# amp-LNA-L-band-TQP3M9037.net
KiCad netlist of a schematic drawn in EAGLE
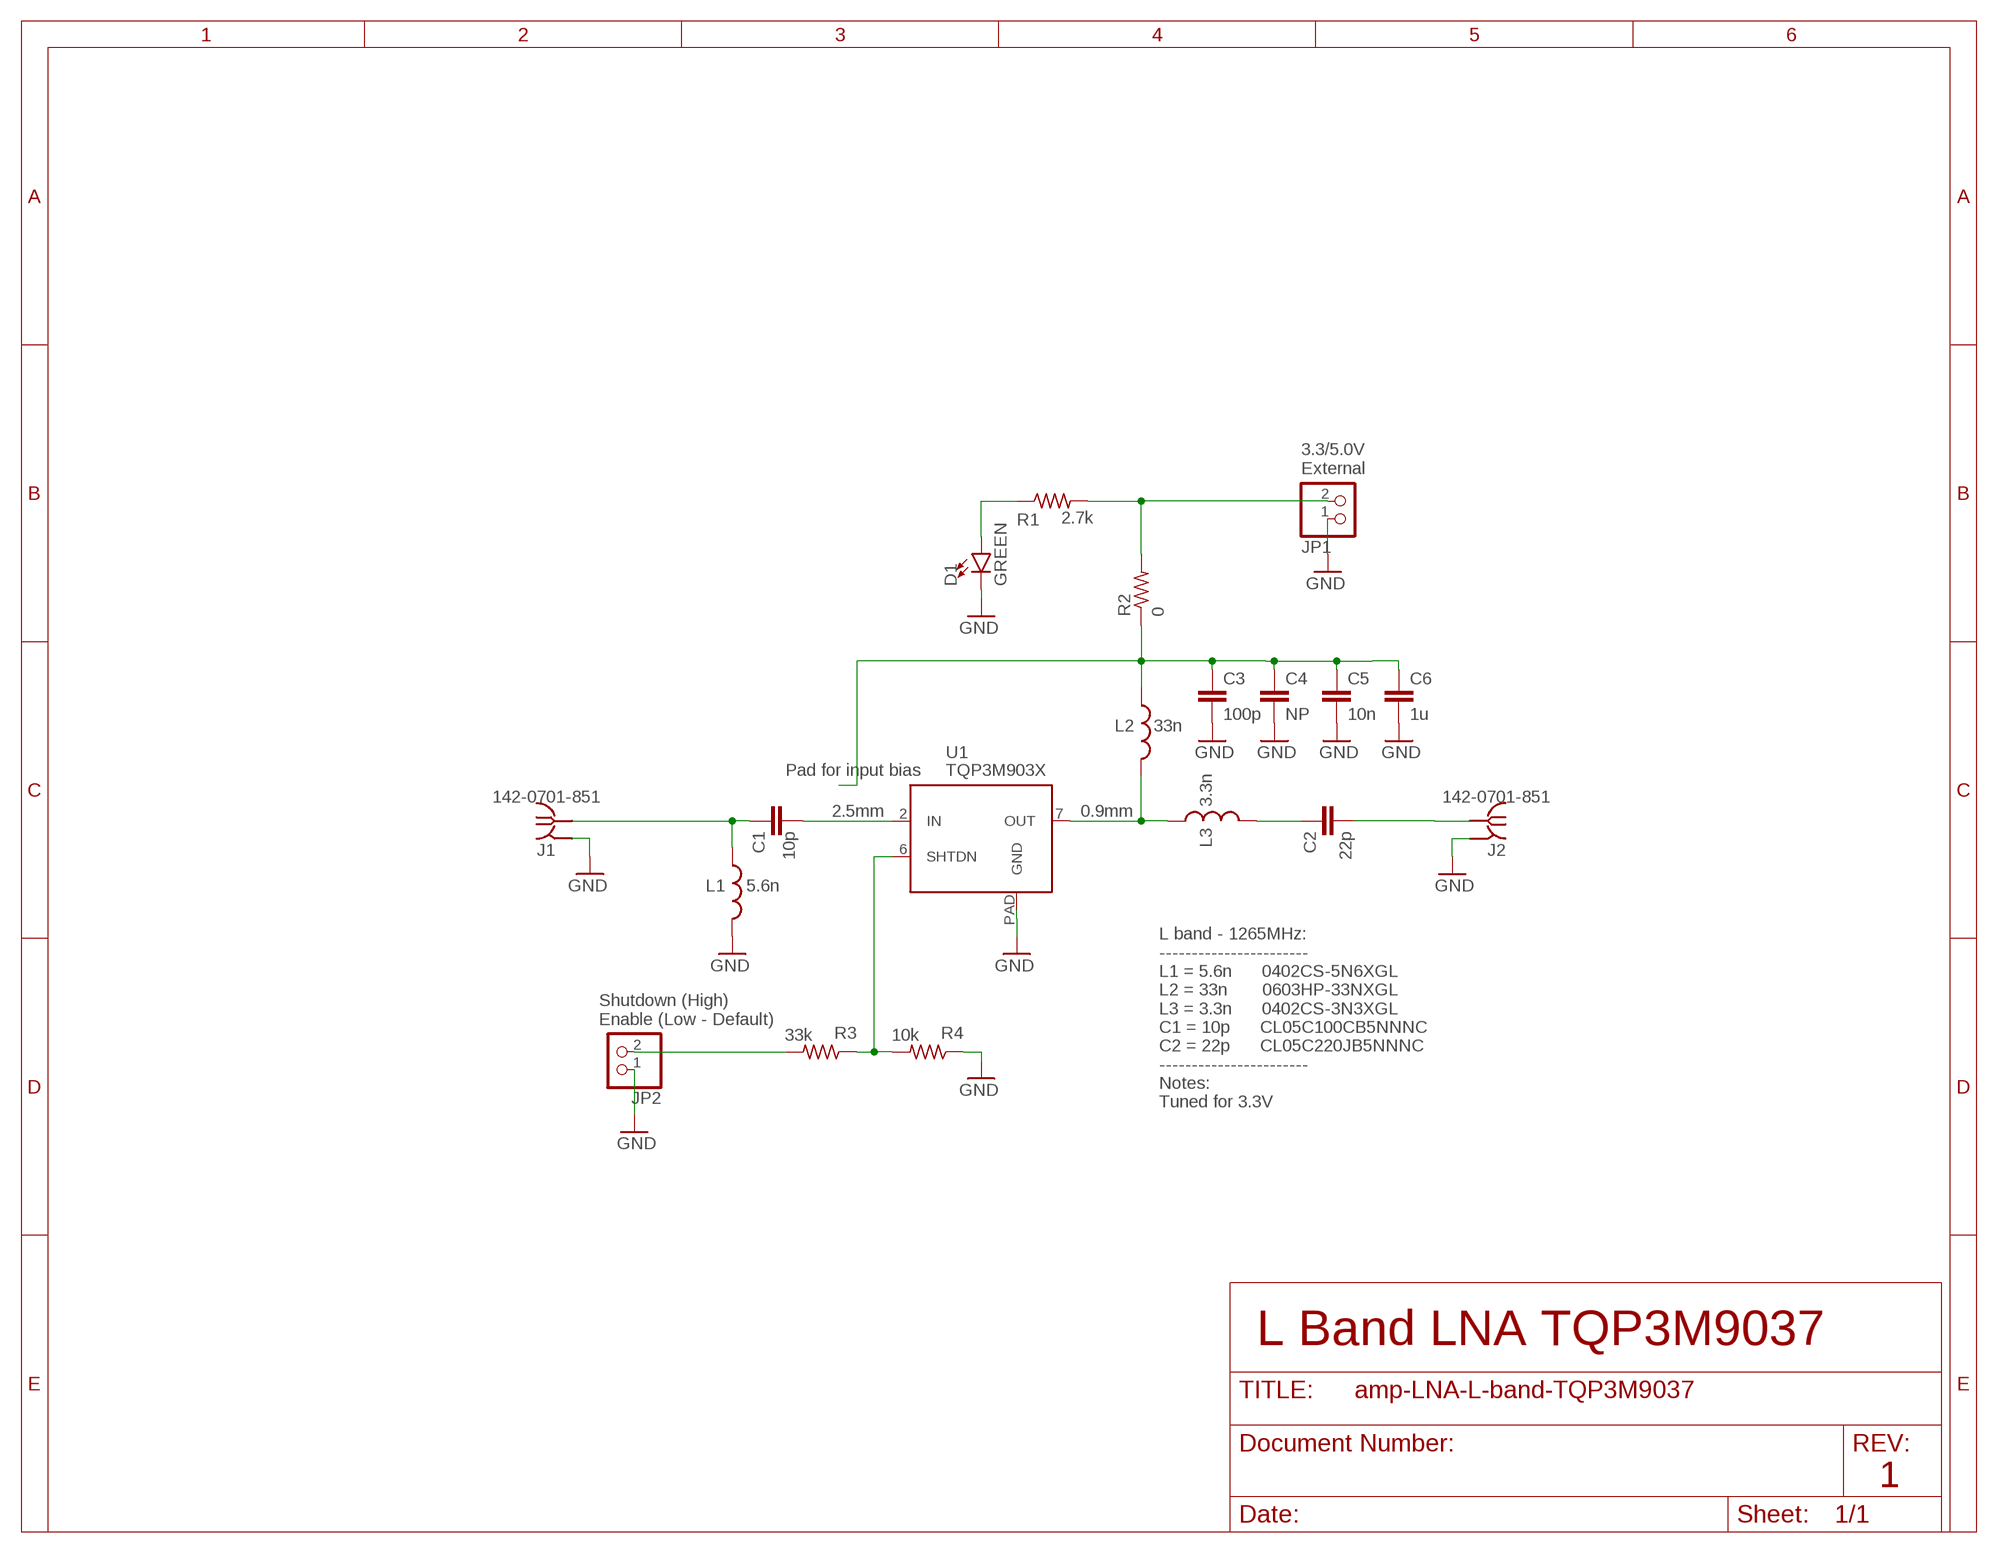
[diagram p0: schematic, sheet 1]

(export (version "E")
  (design (tool "Eeschema 10.0.6"))
  (components
    (comp (ref "C1")
      (value "10p")
      (footprint "eagle-import:.0402-C-NOSILK")
      (libsource (lib "eagle-import") (part "C-EU0402-C-NOSILK"))
    )
    (comp (ref "C2")
      (value "22p")
      (footprint "eagle-import:.0402-C-NOSILK")
      (libsource (lib "eagle-import") (part "C-EU0402-C-NOSILK"))
    )
    (comp (ref "C3")
      (value "100p")
      (footprint "eagle-import:.0603-B-NOSILK")
      (libsource (lib "eagle-import") (part "C-EU0603-B-NOSILK"))
    )
    (comp (ref "C4")
      (value "NP")
      (footprint "eagle-import:.0603-B-NOSILK")
      (libsource (lib "eagle-import") (part "C-EU0603-B-NOSILK"))
    )
    (comp (ref "C5")
      (value "10n")
      (footprint "eagle-import:.0603-B-NOSILK")
      (libsource (lib "eagle-import") (part "C-EU0603-B-NOSILK"))
    )
    (comp (ref "C6")
      (value "1u")
      (footprint "eagle-import:.0603-B-NOSILK")
      (libsource (lib "eagle-import") (part "C-EU0603-B-NOSILK"))
    )
    (comp (ref "D1")
      (value "GREEN")
      (footprint "eagle-import:LED-0603")
      (libsource (lib "eagle-import") (part "LED-GREEN0603"))
    )
    (comp (ref "J1")
      (value "142-0701-851")
      (footprint "eagle-import:142-0701-851")
      (libsource (lib "eagle-import") (part "142-0701-851"))
    )
    (comp (ref "J2")
      (value "142-0701-851")
      (footprint "eagle-import:142-0701-851")
      (libsource (lib "eagle-import") (part "142-0701-851"))
    )
    (comp (ref "JP1")
      (value "PINHD-1X2")
      (footprint "eagle-import:1X02")
      (libsource (lib "eagle-import") (part "PINHD-1X2"))
    )
    (comp (ref "JP2")
      (value "PINHD-1X2")
      (footprint "eagle-import:1X02")
      (libsource (lib "eagle-import") (part "PINHD-1X2"))
    )
    (comp (ref "L1")
      (value "5.6n")
      (footprint "eagle-import:.0402-C-NOSILK")
      (libsource (lib "eagle-import") (part "L-US0402-C-NOSILK"))
    )
    (comp (ref "L2")
      (value "33n")
      (footprint "eagle-import:.0603-C-NOSILK")
      (libsource (lib "eagle-import") (part "L-US0603-C-NOSILK"))
    )
    (comp (ref "L3")
      (value "3.3n")
      (footprint "eagle-import:.0402-C-NOSILK")
      (libsource (lib "eagle-import") (part "L-US0402-C-NOSILK"))
    )
    (comp (ref "R1")
      (value "2.7k")
      (footprint "eagle-import:.0603-B-NOSILK")
      (libsource (lib "eagle-import") (part "R-US_0603-B-NOSILK"))
    )
    (comp (ref "R2")
      (value "0")
      (footprint "eagle-import:.0603-B-NOSILK")
      (libsource (lib "eagle-import") (part "R-US_0603-B-NOSILK"))
    )
    (comp (ref "R3")
      (value "33k")
      (footprint "eagle-import:.0603-B-NOSILK")
      (libsource (lib "eagle-import") (part "R-US_0603-B-NOSILK"))
    )
    (comp (ref "R4")
      (value "10k")
      (footprint "eagle-import:.0603-B-NOSILK")
      (libsource (lib "eagle-import") (part "R-US_0603-B-NOSILK"))
    )
    (comp (ref "U1")
      (value "TQP3M903X")
      (footprint "eagle-import:DFN8-2X2-WITH-PAD")
      (libsource (lib "eagle-import") (part "TQP3M903X"))
    )
  )
  (nets
    (net (code "1") (name "GND") (class "Default")
      (node (ref "C3") (pin "2") (pinfunction "2_2") (pintype "passive"))
      (node (ref "C4") (pin "2") (pinfunction "2_2") (pintype "passive"))
      (node (ref "C5") (pin "2") (pinfunction "2_2") (pintype "passive"))
      (node (ref "C6") (pin "2") (pinfunction "2_2") (pintype "passive"))
      (node (ref "D1") (pin "C") (pinfunction "C_C") (pintype "passive"))
      (node (ref "J1") (pin "GND1") (pinfunction "GND_GND1") (pintype "bidirectional"))
      (node (ref "J1") (pin "GND2") (pinfunction "GND_GND2") (pintype "bidirectional"))
      (node (ref "J1") (pin "GND3") (pinfunction "GND_GND3") (pintype "bidirectional"))
      (node (ref "J1") (pin "GND4") (pinfunction "GND_GND4") (pintype "bidirectional"))
      (node (ref "J2") (pin "GND1") (pinfunction "GND_GND1") (pintype "bidirectional"))
      (node (ref "J2") (pin "GND2") (pinfunction "GND_GND2") (pintype "bidirectional"))
      (node (ref "J2") (pin "GND3") (pinfunction "GND_GND3") (pintype "bidirectional"))
      (node (ref "J2") (pin "GND4") (pinfunction "GND_GND4") (pintype "bidirectional"))
      (node (ref "JP1") (pin "1") (pinfunction "1_1") (pintype "passive"))
      (node (ref "JP2") (pin "1") (pinfunction "1_1") (pintype "passive"))
      (node (ref "L1") (pin "2") (pinfunction "2_2") (pintype "passive"))
      (node (ref "R4") (pin "1") (pinfunction "1_1") (pintype "passive"))
      (node (ref "U1") (pin "PAD") (pinfunction "GND_PAD") (pintype "power_in"))
    )
    (net (code "2") (name "Net-(C2-Pad1)") (class "Default")
      (node (ref "C2") (pin "1") (pinfunction "1_1") (pintype "passive"))
      (node (ref "L3") (pin "2") (pinfunction "2_2") (pintype "passive"))
    )
    (net (code "3") (name "Net-(C3-Pad1)") (class "Default")
      (node (ref "C3") (pin "1") (pinfunction "1_1") (pintype "passive"))
      (node (ref "C4") (pin "1") (pinfunction "1_1") (pintype "passive"))
      (node (ref "C5") (pin "1") (pinfunction "1_1") (pintype "passive"))
      (node (ref "C6") (pin "1") (pinfunction "1_1") (pintype "passive"))
      (node (ref "L2") (pin "1") (pinfunction "1_1") (pintype "passive"))
      (node (ref "R2") (pin "1") (pinfunction "1_1") (pintype "passive"))
    )
    (net (code "4") (name "Net-(D1-PadA)") (class "Default")
      (node (ref "D1") (pin "A") (pinfunction "A_A") (pintype "passive"))
      (node (ref "R1") (pin "1") (pinfunction "1_1") (pintype "passive"))
    )
    (net (code "5") (name "Net-(J1-RF)") (class "Default")
      (node (ref "C1") (pin "1") (pinfunction "1_1") (pintype "passive"))
      (node (ref "J1") (pin "RF1") (pinfunction "RF_RF1") (pintype "bidirectional"))
      (node (ref "L1") (pin "1") (pinfunction "1_1") (pintype "passive"))
    )
    (net (code "6") (name "Net-(J2-RF)") (class "Default")
      (node (ref "C2") (pin "2") (pinfunction "2_2") (pintype "passive"))
      (node (ref "J2") (pin "RF1") (pinfunction "RF_RF1") (pintype "bidirectional"))
    )
    (net (code "7") (name "Net-(JP1-Pad2)") (class "Default")
      (node (ref "JP1") (pin "2") (pinfunction "2_2") (pintype "passive"))
      (node (ref "R1") (pin "2") (pinfunction "2_2") (pintype "passive"))
      (node (ref "R2") (pin "2") (pinfunction "2_2") (pintype "passive"))
    )
    (net (code "8") (name "Net-(JP2-Pad2)") (class "Default")
      (node (ref "JP2") (pin "2") (pinfunction "2_2") (pintype "passive"))
      (node (ref "R3") (pin "2") (pinfunction "2_2") (pintype "passive"))
    )
    (net (code "9") (name "Net-(U1-IN)") (class "Default")
      (node (ref "C1") (pin "2") (pinfunction "2_2") (pintype "passive"))
      (node (ref "U1") (pin "2") (pinfunction "IN_2") (pintype "input"))
    )
    (net (code "10") (name "Net-(U1-OUT)") (class "Default")
      (node (ref "L2") (pin "2") (pinfunction "2_2") (pintype "passive"))
      (node (ref "L3") (pin "1") (pinfunction "1_1") (pintype "passive"))
      (node (ref "U1") (pin "7") (pinfunction "OUT_7") (pintype "output"))
    )
    (net (code "11") (name "Net-(U1-SHTDN)") (class "Default")
      (node (ref "R3") (pin "1") (pinfunction "1_1") (pintype "passive"))
      (node (ref "R4") (pin "2") (pinfunction "2_2") (pintype "passive"))
      (node (ref "U1") (pin "6") (pinfunction "SHTDN_6") (pintype "input"))
    )
  )
)
